# riffle-CTD-REVA.net
KiCad netlist of a schematic drawn in EAGLE
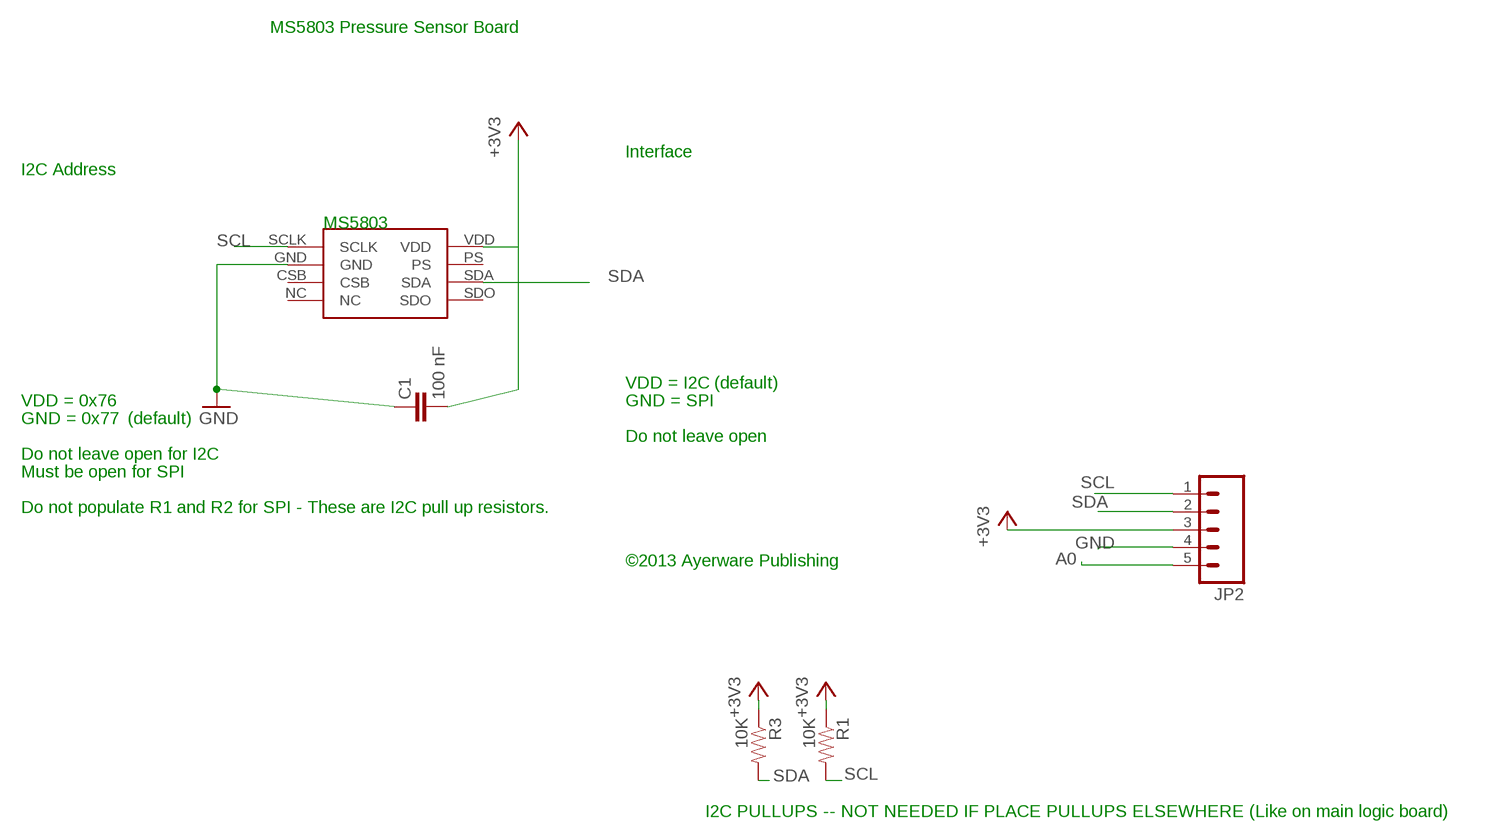
[diagram p0: schematic, sheet 1]

(export (version "E")
  (design (tool "Eeschema 10.0.6"))
  (components
    (comp (ref "C1")
      (value "100 nF")
      (footprint "eagle-import:0402-CAP")
      (libsource (lib "eagle-import") (part "CAP0402-CAP"))
    )
    (comp (ref "JP2")
      (value "M05PTH")
      (footprint "eagle-import:1X05")
      (libsource (lib "eagle-import") (part "M05PTH"))
    )
    (comp (ref "MS5803")
      (value "MS5803-14BA")
      (footprint "eagle-import:MS5803-14BA")
      (libsource (lib "eagle-import") (part "MS5803-14BA"))
    )
    (comp (ref "R1")
      (value "10K")
      (footprint "eagle-import:0402-RES")
      (libsource (lib "eagle-import") (part "RESISTOR0402-RES"))
    )
    (comp (ref "R3")
      (value "10K")
      (footprint "eagle-import:0402-RES")
      (libsource (lib "eagle-import") (part "RESISTOR0402-RES"))
    )
  )
  (nets
    (net (code "1") (name "+3V3") (class "Default")
      (node (ref "C1") (pin "1") (pinfunction "1_1") (pintype "passive"))
      (node (ref "JP2") (pin "3") (pinfunction "3_3") (pintype "passive"))
      (node (ref "MS5803") (pin "VDD") (pinfunction "VDD_VDD") (pintype "bidirectional"))
      (node (ref "R1") (pin "1") (pinfunction "1_1") (pintype "passive"))
      (node (ref "R3") (pin "1") (pinfunction "1_1") (pintype "passive"))
    )
    (net (code "2") (name "/A0") (class "Default")
      (node (ref "JP2") (pin "5") (pinfunction "5_5") (pintype "passive"))
    )
    (net (code "3") (name "/SCL") (class "Default")
      (node (ref "JP2") (pin "1") (pinfunction "1_1") (pintype "passive"))
      (node (ref "MS5803") (pin "SCLK") (pinfunction "SCLK_SCLK") (pintype "bidirectional"))
      (node (ref "R1") (pin "2") (pinfunction "2_2") (pintype "passive"))
    )
    (net (code "4") (name "/SDA") (class "Default")
      (node (ref "JP2") (pin "2") (pinfunction "2_2") (pintype "passive"))
      (node (ref "MS5803") (pin "SDA") (pinfunction "SDA_SDA") (pintype "bidirectional"))
      (node (ref "R3") (pin "2") (pinfunction "2_2") (pintype "passive"))
    )
    (net (code "5") (name "GND") (class "Default")
      (node (ref "C1") (pin "2") (pinfunction "2_2") (pintype "passive"))
      (node (ref "JP2") (pin "4") (pinfunction "4_4") (pintype "passive"))
      (node (ref "MS5803") (pin "GND") (pinfunction "GND_GND") (pintype "bidirectional"))
    )
    (net (code "6") (name "unconnected-(MS5803-PadCSB)") (class "Default")
      (node (ref "MS5803") (pin "CSB") (pinfunction "CSB_CSB") (pintype "bidirectional"))
    )
    (net (code "7") (name "unconnected-(MS5803-PadNC)") (class "Default")
      (node (ref "MS5803") (pin "NC") (pinfunction "NC_NC") (pintype "bidirectional"))
    )
    (net (code "8") (name "unconnected-(MS5803-PadPS)") (class "Default")
      (node (ref "MS5803") (pin "PS") (pinfunction "PS_PS") (pintype "bidirectional"))
    )
    (net (code "9") (name "unconnected-(MS5803-PadSDO)") (class "Default")
      (node (ref "MS5803") (pin "SDO") (pinfunction "SDO_SDO") (pintype "bidirectional"))
    )
  )
)
